# Top_Sheet.net
KiCad netlist of a schematic drawn in Altium Designer
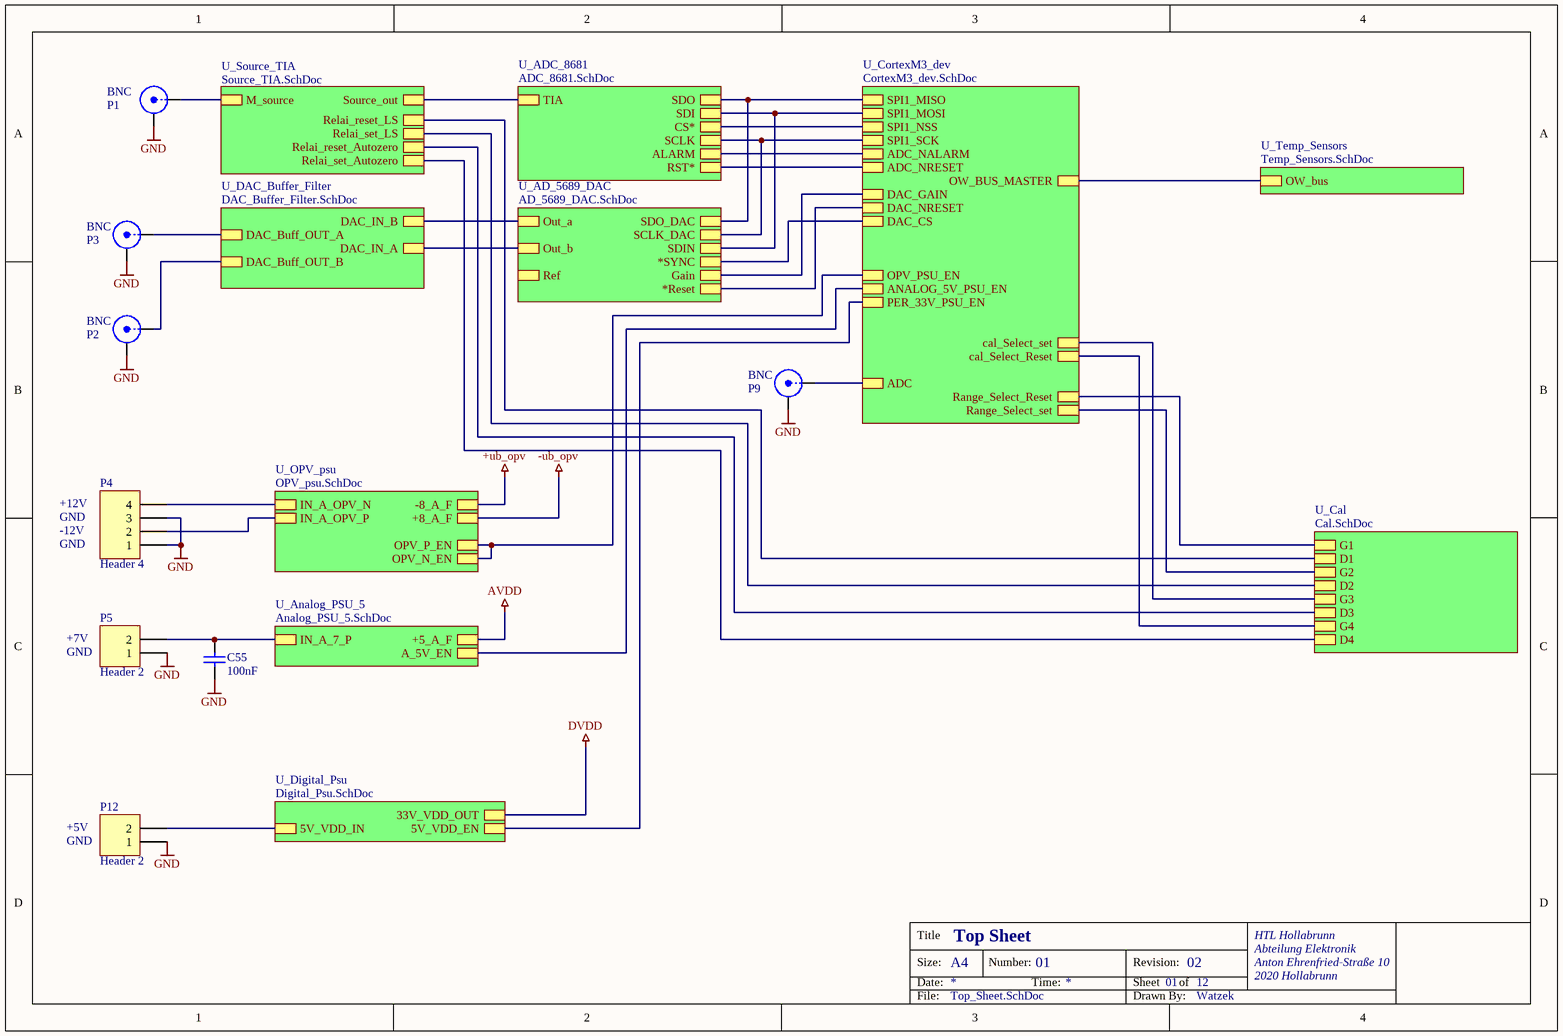
[diagram p0: Top_Sheet.SchDoc]

(export (version "E")
  (design (tool "Eeschema 10.0.6"))
  (components
    (comp (ref "C55")
      (value "100nF")
      (footprint "C1206-KUE")
      (description "Capacitor")
      (fields (field (name "MANUFACTURER") "Kemet") (field (name "PUBLISHER") "Altium Limited"))
      (libsource (lib "ExtrapartsKUE_V01") (part "Capacitor"))
    )
    (comp (ref "P1")
      (value "BNC")
      (footprint "BNC_RA CON")
      (description "BNC Elbow Connector")
      (fields (field (name "PUBLISHER") "Altium Limited"))
      (libsource (lib "Miscellaneous Connectors") (part "BNC"))
    )
    (comp (ref "P2")
      (value "BNC")
      (footprint "BNC_RA CON")
      (description "BNC Elbow Connector")
      (fields (field (name "PUBLISHER") "Altium Limited"))
      (libsource (lib "Miscellaneous Connectors") (part "BNC"))
    )
    (comp (ref "P3")
      (value "BNC")
      (footprint "BNC_RA CON")
      (description "BNC Elbow Connector")
      (fields (field (name "PUBLISHER") "Altium Limited"))
      (libsource (lib "Miscellaneous Connectors") (part "BNC"))
    )
    (comp (ref "P4")
      (value "Header 4")
      (footprint "HDR1X4")
      (description "Header, 4-Pin")
      (fields (field (name "PUBLISHER") "Altium Limited"))
      (libsource (lib "Miscellaneous Connectors") (part "Header 4"))
    )
    (comp (ref "P5")
      (value "Header 2")
      (footprint "HDR1X2")
      (description "Header, 2-Pin")
      (fields (field (name "PUBLISHER") "Altium Limited"))
      (libsource (lib "Miscellaneous Connectors") (part "Header 2"))
    )
    (comp (ref "P9")
      (value "BNC")
      (footprint "BNC_RA CON")
      (description "BNC Elbow Connector")
      (fields (field (name "PUBLISHER") "Altium Limited"))
      (libsource (lib "Miscellaneous Connectors") (part "BNC"))
    )
    (comp (ref "P12")
      (value "Header 2")
      (footprint "HDR1X2")
      (description "Header, 2-Pin")
      (fields (field (name "PUBLISHER") "Altium Limited"))
      (libsource (lib "Miscellaneous Connectors") (part "Header 2"))
    )
  )
  (nets
    (net (code "6") (name "/5V_VDD_IN") (class "Default")
      (node (ref "P12") (pin "2") (pinfunction "2_2") (pintype "passive"))
    )
    (net (code "7") (name "/ADC") (class "Default")
      (node (ref "P9") (pin "1") (pinfunction "X_1") (pintype "passive"))
    )
    (net (code "16") (name "/DAC_Buff_OUT_A") (class "Default")
      (node (ref "P3") (pin "1") (pinfunction "X_1") (pintype "passive"))
    )
    (net (code "17") (name "/DAC_Buff_OUT_B") (class "Default")
      (node (ref "P2") (pin "1") (pinfunction "X_1") (pintype "passive"))
    )
    (net (code "25") (name "/IN_A_7_P") (class "Default")
      (node (ref "C55") (pin "2") (pinfunction "2_2") (pintype "passive"))
      (node (ref "P5") (pin "2") (pinfunction "2_2") (pintype "passive"))
    )
    (net (code "26") (name "/IN_A_OPV_N") (class "Default")
      (node (ref "P4") (pin "4") (pinfunction "4_4") (pintype "passive"))
    )
    (net (code "27") (name "/IN_A_OPV_P") (class "Default")
      (node (ref "P4") (pin "2") (pinfunction "2_2") (pintype "passive"))
    )
    (net (code "28") (name "/M_source") (class "Default")
      (node (ref "P1") (pin "1") (pinfunction "X_1") (pintype "passive"))
    )
    (net (code "38") (name "GND") (class "Default")
      (node (ref "C55") (pin "1") (pinfunction "1_1") (pintype "passive"))
      (node (ref "P1") (pin "2") (pinfunction "Y_2") (pintype "passive"))
      (node (ref "P12") (pin "1") (pinfunction "1_1") (pintype "passive"))
      (node (ref "P2") (pin "2") (pinfunction "Y_2") (pintype "passive"))
      (node (ref "P3") (pin "2") (pinfunction "Y_2") (pintype "passive"))
      (node (ref "P4") (pin "1") (pinfunction "1_1") (pintype "passive"))
      (node (ref "P4") (pin "3") (pinfunction "3_3") (pintype "passive"))
      (node (ref "P5") (pin "1") (pinfunction "1_1") (pintype "passive"))
      (node (ref "P9") (pin "2") (pinfunction "Y_2") (pintype "passive"))
    )
  )
)
